# untitled.net
KiCad netlist of a schematic drawn in EAGLE
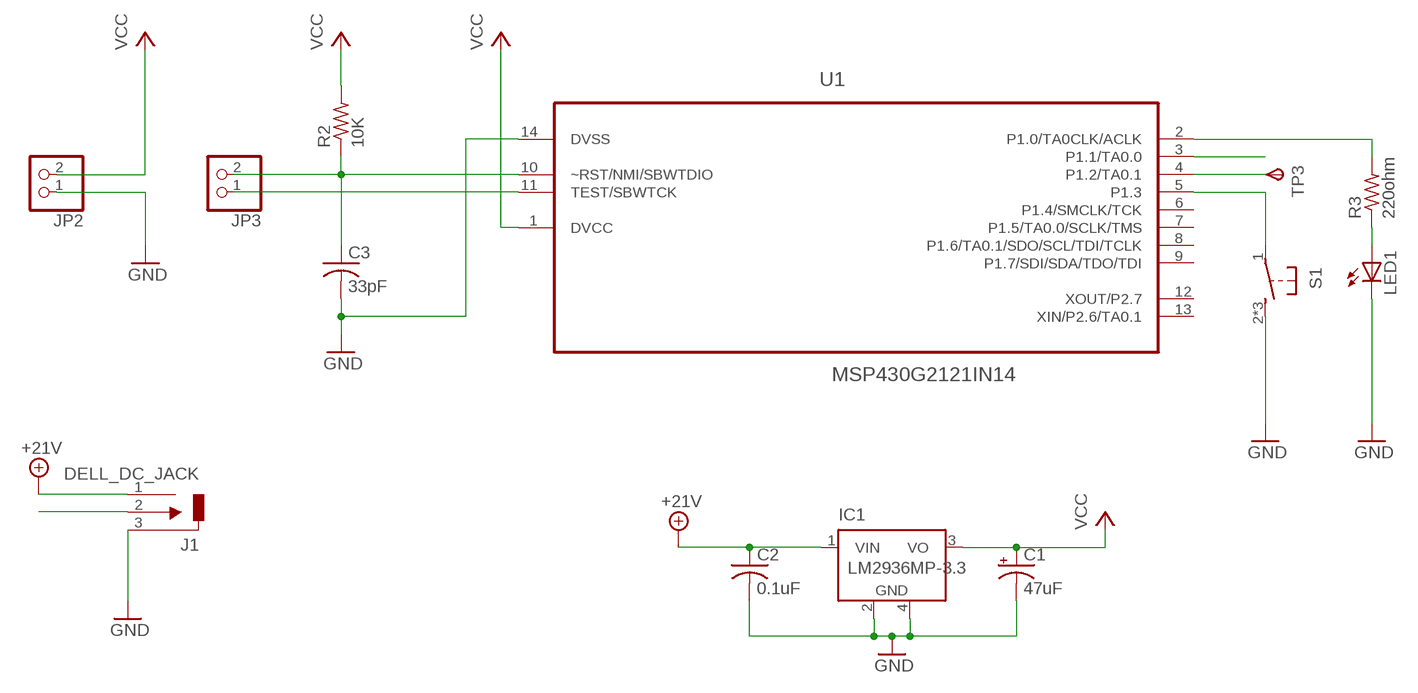
[diagram p0: schematic, sheet 1]

(export (version "E")
  (design (tool "Eeschema 10.0.6"))
  (components
    (comp (ref "C1")
      (value "47uF")
      (footprint "eagle-import:E2,5-5")
      (libsource (lib "eagle-import") (part "CPOL-USE2.5-5"))
    )
    (comp (ref "C2")
      (value "0.1uF")
      (footprint "eagle-import:C025-025X050")
      (libsource (lib "eagle-import") (part "C-US025-025X050"))
    )
    (comp (ref "C3")
      (value "33pF")
      (footprint "eagle-import:C025-025X050")
      (libsource (lib "eagle-import") (part "C-US025-025X050"))
    )
    (comp (ref "IC1")
      (value "LM2936MP-3.3")
      (footprint "eagle-import:SOT223")
      (fields (field (name "MF") "NATIONAL SEMICONDUCTOR") (field (name "MPN") "LM2936MP-3.3/NOPB"))
      (libsource (lib "eagle-import") (part "LM2936MP?-3.3"))
    )
    (comp (ref "J1")
      (value "DELL_DC_JACK")
      (footprint "eagle-import:DELL_DC_JACK")
      (libsource (lib "eagle-import") (part "DELL_DC_JACK"))
    )
    (comp (ref "JP2")
      (value "PINHD-1X2")
      (footprint "eagle-import:1X02")
      (libsource (lib "eagle-import") (part "PINHD-1X2"))
    )
    (comp (ref "JP3")
      (value "PINHD-1X2")
      (footprint "eagle-import:1X02")
      (libsource (lib "eagle-import") (part "PINHD-1X2"))
    )
    (comp (ref "LED1")
      (value "LED3MM")
      (footprint "eagle-import:LED3MM")
      (libsource (lib "eagle-import") (part "LED3MM"))
    )
    (comp (ref "R2")
      (value "10K")
      (footprint "eagle-import:0207_12")
      (libsource (lib "eagle-import") (part "R-US_0207/12"))
    )
    (comp (ref "R3")
      (value "220ohm")
      (footprint "eagle-import:0207_12")
      (libsource (lib "eagle-import") (part "R-US_0207/12"))
    )
    (comp (ref "S1")
      (value "31-XX")
      (footprint "eagle-import:B3F-31XX")
      (fields (field (name "MPN") "B3F-3100"))
      (libsource (lib "eagle-import") (part "31-XX"))
    )
    (comp (ref "TP3")
      (value "TPSPAD1-13")
      (footprint "eagle-import:P1-13")
      (libsource (lib "eagle-import") (part "TPSPAD1-13"))
    )
    (comp (ref "U1")
      (value "MSP430G2121IN14")
      (footprint "eagle-import:DIP254P762X508-14")
      (libsource (lib "eagle-import") (part "MSP430G2121IN14"))
    )
  )
  (nets
    (net (code "1") (name "+21V") (class "Default")
      (node (ref "C2") (pin "1") (pinfunction "1_1") (pintype "passive"))
      (node (ref "IC1") (pin "1") (pinfunction "VIN_1") (pintype "input"))
      (node (ref "J1") (pin "1") (pinfunction "VIN_1") (pintype "passive"))
    )
    (net (code "2") (name "/SIG") (class "Default")
      (node (ref "J1") (pin "2") (pinfunction "SIG_2") (pintype "passive"))
      (node (ref "U1") (pin "3") (pinfunction "P1.1/TA0.0_3") (pintype "bidirectional"))
    )
    (net (code "3") (name "GND") (class "Default")
      (node (ref "C1") (pin "-") (pinfunction "-_-") (pintype "passive"))
      (node (ref "C2") (pin "2") (pinfunction "2_2") (pintype "passive"))
      (node (ref "C3") (pin "2") (pinfunction "2_2") (pintype "passive"))
      (node (ref "IC1") (pin "2") (pinfunction "GND_2") (pintype "passive"))
      (node (ref "IC1") (pin "4") (pinfunction "GND_4") (pintype "passive"))
      (node (ref "J1") (pin "3") (pinfunction "GND_3") (pintype "passive"))
      (node (ref "JP2") (pin "1") (pinfunction "1_1") (pintype "passive"))
      (node (ref "LED1") (pin "K") (pinfunction "C_K") (pintype "passive"))
      (node (ref "S1") (pin "2") (pinfunction "S_2") (pintype "passive"))
      (node (ref "S1") (pin "3") (pinfunction "S_3") (pintype "passive"))
      (node (ref "S1") (pin "4") (pinfunction "S_4") (pintype "passive"))
      (node (ref "U1") (pin "14") (pinfunction "DVSS_14") (pintype "power_in"))
    )
    (net (code "4") (name "Net-(LED1-PadA)") (class "Default")
      (node (ref "LED1") (pin "A") (pinfunction "A_A") (pintype "passive"))
      (node (ref "R3") (pin "1") (pinfunction "1_1") (pintype "passive"))
    )
    (net (code "5") (name "Net-(S1-P)") (class "Default")
      (node (ref "S1") (pin "1") (pinfunction "P_1") (pintype "passive"))
      (node (ref "U1") (pin "5") (pinfunction "P1.3_5") (pintype "bidirectional"))
    )
    (net (code "6") (name "Net-(TP3-PP)") (class "Default")
      (node (ref "TP3") (pin "TP") (pinfunction "PP_TP") (pintype "input"))
      (node (ref "U1") (pin "4") (pinfunction "P1.2/TA0.1_4") (pintype "bidirectional"))
    )
    (net (code "7") (name "Net-(U1-P1.0{slash}TA0CLK{slash}ACLK)") (class "Default")
      (node (ref "R3") (pin "2") (pinfunction "2_2") (pintype "passive"))
      (node (ref "U1") (pin "2") (pinfunction "P1.0/TA0CLK/ACLK_2") (pintype "bidirectional"))
    )
    (net (code "8") (name "Net-(U1-TEST{slash}SBWTCK)") (class "Default")
      (node (ref "JP3") (pin "1") (pinfunction "1_1") (pintype "passive"))
      (node (ref "U1") (pin "11") (pinfunction "TEST/SBWTCK_11") (pintype "input"))
    )
    (net (code "9") (name "Net-(U1-~{RST{slash}NMI{slash}SBWTDIO})") (class "Default")
      (node (ref "C3") (pin "1") (pinfunction "1_1") (pintype "passive"))
      (node (ref "JP3") (pin "2") (pinfunction "2_2") (pintype "passive"))
      (node (ref "R2") (pin "1") (pinfunction "1_1") (pintype "passive"))
      (node (ref "U1") (pin "10") (pinfunction "~{RST/NMI/SBWTDIO}_10") (pintype "input"))
    )
    (net (code "10") (name "VCC") (class "Default")
      (node (ref "C1") (pin "+") (pinfunction "+_+") (pintype "passive"))
      (node (ref "IC1") (pin "3") (pinfunction "VO_3") (pintype "passive"))
      (node (ref "JP2") (pin "2") (pinfunction "2_2") (pintype "passive"))
      (node (ref "R2") (pin "2") (pinfunction "2_2") (pintype "passive"))
      (node (ref "U1") (pin "1") (pinfunction "DVCC_1") (pintype "power_in"))
    )
    (net (code "11") (name "unconnected-(U1-P1.4{slash}SMCLK{slash}TCK-Pad6)") (class "Default")
      (node (ref "U1") (pin "6") (pinfunction "P1.4/SMCLK/TCK_6") (pintype "bidirectional"))
    )
    (net (code "12") (name "unconnected-(U1-P1.5{slash}TA0.0{slash}SCLK{slash}TMS-Pad7)") (class "Default")
      (node (ref "U1") (pin "7") (pinfunction "P1.5/TA0.0/SCLK/TMS_7") (pintype "bidirectional"))
    )
    (net (code "13") (name "unconnected-(U1-P1.6{slash}TA0.1{slash}SDO{slash}SCL{slash}TDI{slash}TCLK-Pad8)") (class "Default")
      (node (ref "U1") (pin "8") (pinfunction "P1.6/TA0.1/SDO/SCL/TDI/TCLK_8") (pintype "bidirectional"))
    )
    (net (code "14") (name "unconnected-(U1-P1.7{slash}SDI{slash}SDA{slash}TDO{slash}TDI-Pad9)") (class "Default")
      (node (ref "U1") (pin "9") (pinfunction "P1.7/SDI/SDA/TDO/TDI_9") (pintype "bidirectional"))
    )
    (net (code "15") (name "unconnected-(U1-XIN{slash}P2.6{slash}TA0.1-Pad13)") (class "Default")
      (node (ref "U1") (pin "13") (pinfunction "XIN/P2.6/TA0.1_13") (pintype "bidirectional"))
    )
    (net (code "16") (name "unconnected-(U1-XOUT{slash}P2.7-Pad12)") (class "Default")
      (node (ref "U1") (pin "12") (pinfunction "XOUT/P2.7_12") (pintype "bidirectional"))
    )
  )
)
